# TRACTIAN_Power.net
KiCad netlist of a schematic drawn in Altium Designer
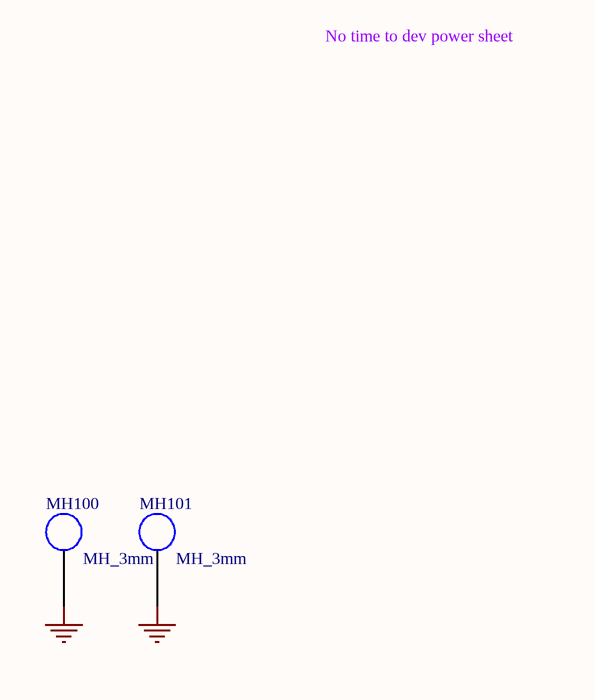
[diagram p0: TRACTIAN_Power.SchDoc]

(export (version "E")
  (design (tool "Eeschema 10.0.6"))
  (components
    (comp (ref "MH100")
      (value "MH_3mm")
      (footprint "MH_3mm")
      (libsource (lib "TRACTIAN-HW-Challenge") (part "MH_3mm"))
    )
    (comp (ref "MH101")
      (value "MH_3mm")
      (footprint "MH_3mm")
      (libsource (lib "TRACTIAN-HW-Challenge") (part "MH_3mm"))
    )
  )
  (nets
    (net (code "1") (name "GND") (class "Default")
      (node (ref "MH100") (pin "1") (pinfunction "MH_1") (pintype "passive"))
      (node (ref "MH101") (pin "1") (pinfunction "MH_1") (pintype "passive"))
    )
  )
)
